# M709B.net
KiCad netlist of a schematic drawn in EAGLE
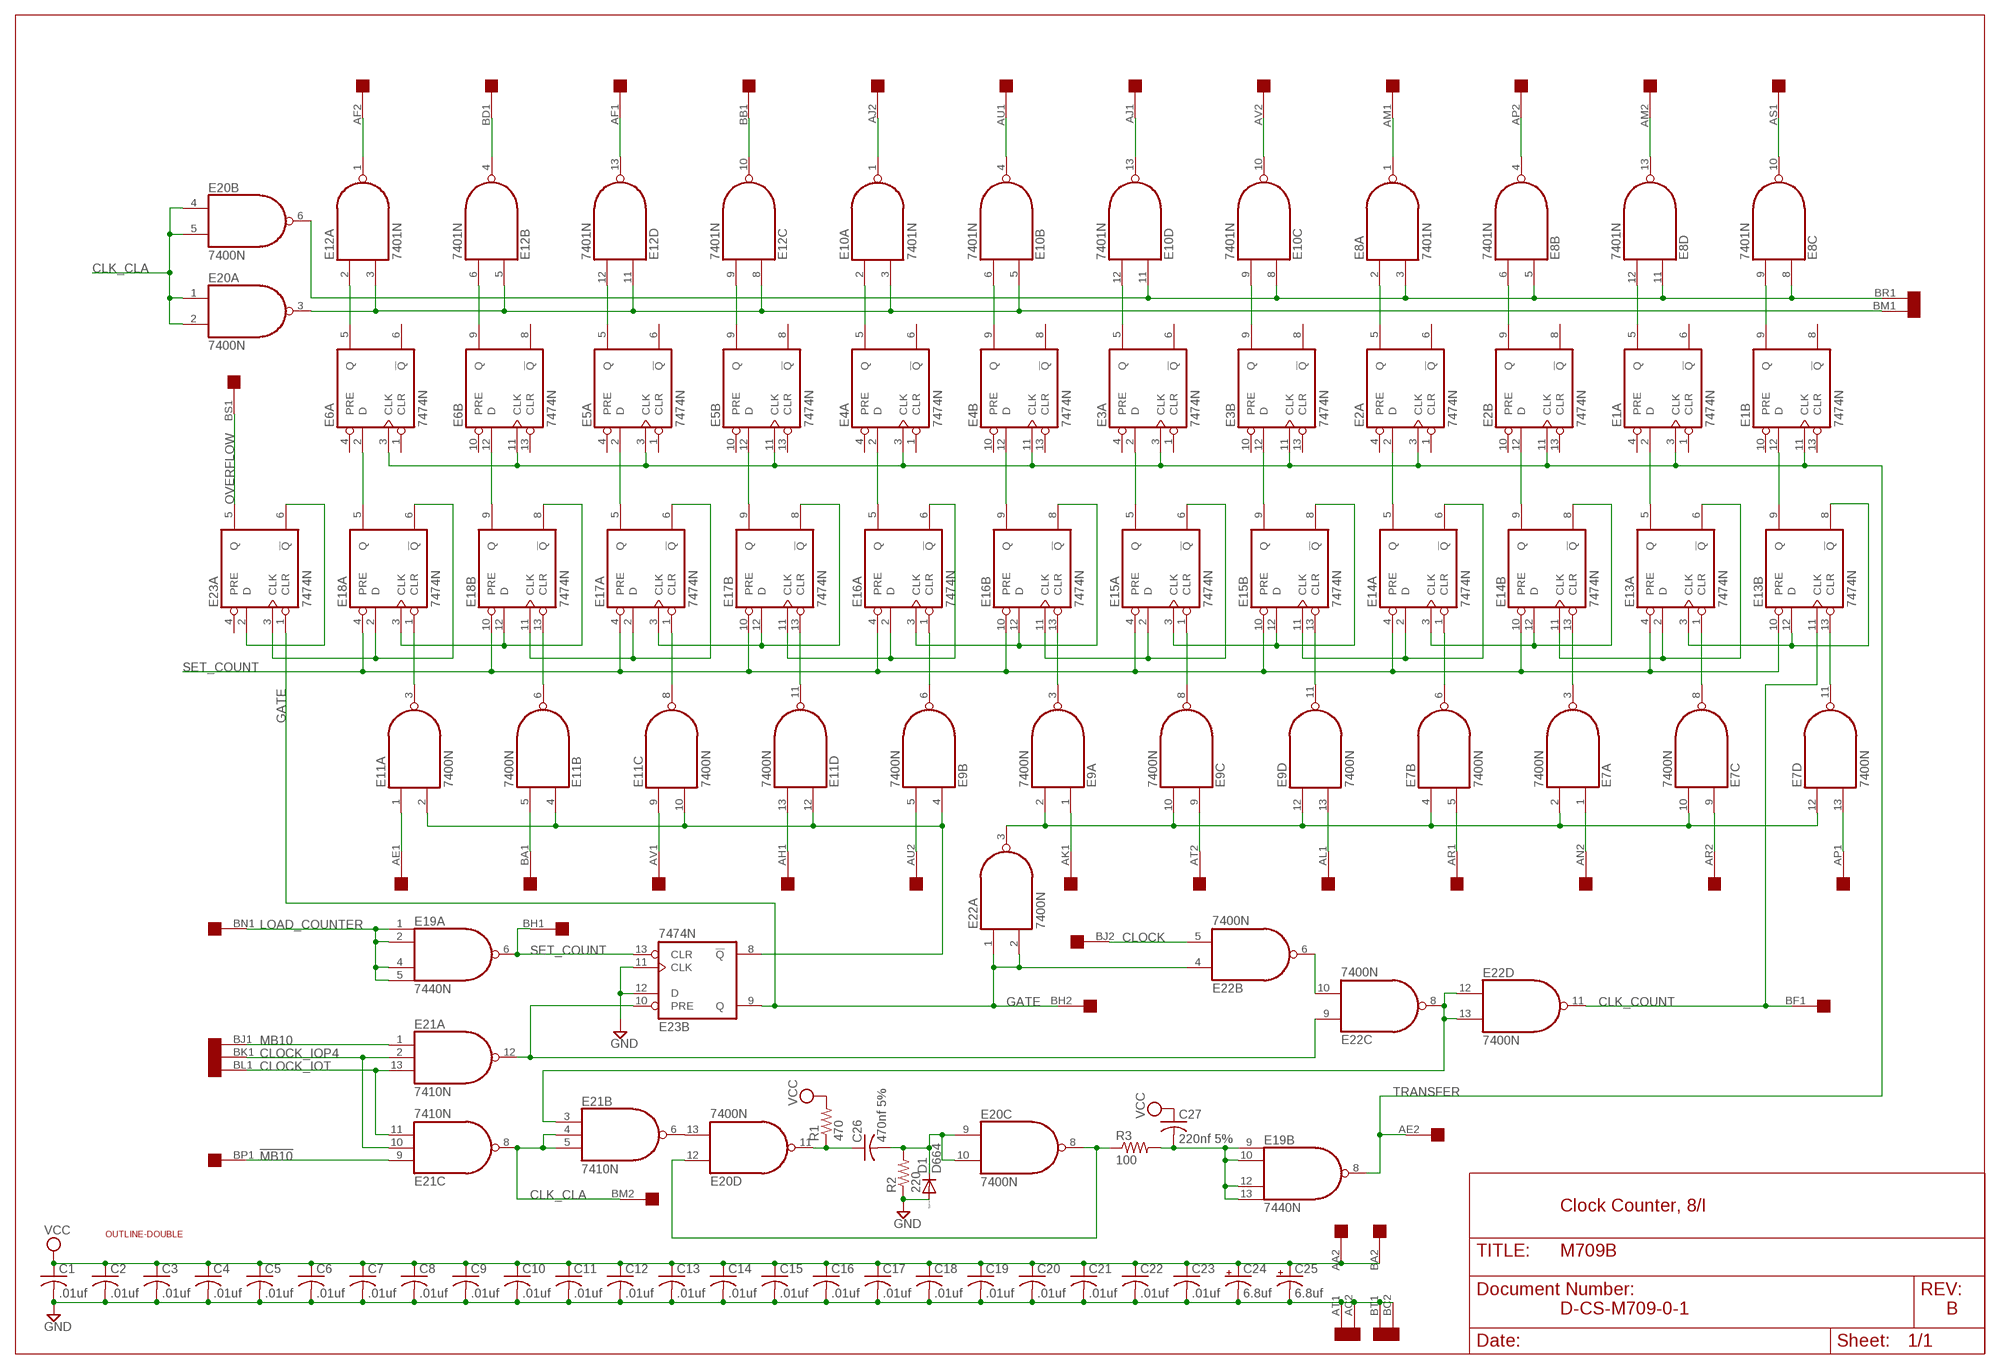
[diagram p0: schematic, sheet 1]

(export (version "E")
  (design (tool "Eeschema 10.0.6"))
  (components
    (comp (ref "C1")
      (value ".01uf")
      (footprint "eagle-import:C050-025X075")
      (libsource (lib "eagle-import") (part "C-US050-025X075"))
    )
    (comp (ref "C2")
      (value ".01uf")
      (footprint "eagle-import:C050-025X075")
      (libsource (lib "eagle-import") (part "C-US050-025X075"))
    )
    (comp (ref "C3")
      (value ".01uf")
      (footprint "eagle-import:C050-025X075")
      (libsource (lib "eagle-import") (part "C-US050-025X075"))
    )
    (comp (ref "C4")
      (value ".01uf")
      (footprint "eagle-import:C050-025X075")
      (libsource (lib "eagle-import") (part "C-US050-025X075"))
    )
    (comp (ref "C5")
      (value ".01uf")
      (footprint "eagle-import:C050-025X075")
      (libsource (lib "eagle-import") (part "C-US050-025X075"))
    )
    (comp (ref "C6")
      (value ".01uf")
      (footprint "eagle-import:C050-025X075")
      (libsource (lib "eagle-import") (part "C-US050-025X075"))
    )
    (comp (ref "C7")
      (value ".01uf")
      (footprint "eagle-import:C050-025X075")
      (libsource (lib "eagle-import") (part "C-US050-025X075"))
    )
    (comp (ref "C8")
      (value ".01uf")
      (footprint "eagle-import:C050-025X075")
      (libsource (lib "eagle-import") (part "C-US050-025X075"))
    )
    (comp (ref "C9")
      (value ".01uf")
      (footprint "eagle-import:C050-025X075")
      (libsource (lib "eagle-import") (part "C-US050-025X075"))
    )
    (comp (ref "C10")
      (value ".01uf")
      (footprint "eagle-import:C050-025X075")
      (libsource (lib "eagle-import") (part "C-US050-025X075"))
    )
    (comp (ref "C11")
      (value ".01uf")
      (footprint "eagle-import:C050-025X075")
      (libsource (lib "eagle-import") (part "C-US050-025X075"))
    )
    (comp (ref "C12")
      (value ".01uf")
      (footprint "eagle-import:C050-025X075")
      (libsource (lib "eagle-import") (part "C-US050-025X075"))
    )
    (comp (ref "C13")
      (value ".01uf")
      (footprint "eagle-import:C050-025X075")
      (libsource (lib "eagle-import") (part "C-US050-025X075"))
    )
    (comp (ref "C14")
      (value ".01uf")
      (footprint "eagle-import:C050-025X075")
      (libsource (lib "eagle-import") (part "C-US050-025X075"))
    )
    (comp (ref "C15")
      (value ".01uf")
      (footprint "eagle-import:C050-025X075")
      (libsource (lib "eagle-import") (part "C-US050-025X075"))
    )
    (comp (ref "C16")
      (value ".01uf")
      (footprint "eagle-import:C050-025X075")
      (libsource (lib "eagle-import") (part "C-US050-025X075"))
    )
    (comp (ref "C17")
      (value ".01uf")
      (footprint "eagle-import:C050-025X075")
      (libsource (lib "eagle-import") (part "C-US050-025X075"))
    )
    (comp (ref "C18")
      (value ".01uf")
      (footprint "eagle-import:C050-025X075")
      (libsource (lib "eagle-import") (part "C-US050-025X075"))
    )
    (comp (ref "C19")
      (value ".01uf")
      (footprint "eagle-import:C050-025X075")
      (libsource (lib "eagle-import") (part "C-US050-025X075"))
    )
    (comp (ref "C20")
      (value ".01uf")
      (footprint "eagle-import:C050-025X075")
      (libsource (lib "eagle-import") (part "C-US050-025X075"))
    )
    (comp (ref "C21")
      (value ".01uf")
      (footprint "eagle-import:C050-025X075")
      (libsource (lib "eagle-import") (part "C-US050-025X075"))
    )
    (comp (ref "C22")
      (value ".01uf")
      (footprint "eagle-import:C050-025X075")
      (libsource (lib "eagle-import") (part "C-US050-025X075"))
    )
    (comp (ref "C23")
      (value ".01uf")
      (footprint "eagle-import:C050-025X075")
      (libsource (lib "eagle-import") (part "C-US050-025X075"))
    )
    (comp (ref "C24")
      (value "6.8uf")
      (footprint "eagle-import:E15-5")
      (libsource (lib "eagle-import") (part "CPOL-USE15-5AXIAL"))
    )
    (comp (ref "C25")
      (value "6.8uf")
      (footprint "eagle-import:E15-5")
      (libsource (lib "eagle-import") (part "CPOL-USE15-5AXIAL"))
    )
    (comp (ref "C26")
      (value "470nf 5%")
      (footprint "eagle-import:C050-025X075")
      (libsource (lib "eagle-import") (part "C-US050-025X075"))
    )
    (comp (ref "C27")
      (value "220nf 5%")
      (footprint "eagle-import:C050-025X075")
      (libsource (lib "eagle-import") (part "C-US050-025X075"))
    )
    (comp (ref "D1")
      (value "D664")
      (footprint "eagle-import:DO35-10")
      (libsource (lib "eagle-import") (part "1N4148DO35-10"))
    )
    (comp (ref "E1")
      (value "7474N")
      (footprint "eagle-import:DIL14")
      (libsource (lib "eagle-import") (part "7474NS"))
    )
    (comp (ref "E2")
      (value "7474N")
      (footprint "eagle-import:DIL14")
      (libsource (lib "eagle-import") (part "7474NS"))
    )
    (comp (ref "E3")
      (value "7474N")
      (footprint "eagle-import:DIL14")
      (libsource (lib "eagle-import") (part "7474NS"))
    )
    (comp (ref "E4")
      (value "7474N")
      (footprint "eagle-import:DIL14")
      (libsource (lib "eagle-import") (part "7474NS"))
    )
    (comp (ref "E5")
      (value "7474N")
      (footprint "eagle-import:DIL14")
      (libsource (lib "eagle-import") (part "7474NS"))
    )
    (comp (ref "E6")
      (value "7474N")
      (footprint "eagle-import:DIL14")
      (libsource (lib "eagle-import") (part "7474NS"))
    )
    (comp (ref "E7")
      (value "7400N")
      (footprint "eagle-import:DIL14")
      (libsource (lib "eagle-import") (part "7400N"))
    )
    (comp (ref "E8")
      (value "7401N")
      (footprint "eagle-import:DIL14")
      (libsource (lib "eagle-import") (part "7401NLS"))
    )
    (comp (ref "E9")
      (value "7400N")
      (footprint "eagle-import:DIL14")
      (libsource (lib "eagle-import") (part "7400N"))
    )
    (comp (ref "E10")
      (value "7401N")
      (footprint "eagle-import:DIL14")
      (libsource (lib "eagle-import") (part "7401NLS"))
    )
    (comp (ref "E11")
      (value "7400N")
      (footprint "eagle-import:DIL14")
      (libsource (lib "eagle-import") (part "7400N"))
    )
    (comp (ref "E12")
      (value "7401N")
      (footprint "eagle-import:DIL14")
      (libsource (lib "eagle-import") (part "7401NLS"))
    )
    (comp (ref "E13")
      (value "7474N")
      (footprint "eagle-import:DIL14")
      (libsource (lib "eagle-import") (part "7474NS"))
    )
    (comp (ref "E14")
      (value "7474N")
      (footprint "eagle-import:DIL14")
      (libsource (lib "eagle-import") (part "7474NS"))
    )
    (comp (ref "E15")
      (value "7474N")
      (footprint "eagle-import:DIL14")
      (libsource (lib "eagle-import") (part "7474NS"))
    )
    (comp (ref "E16")
      (value "7474N")
      (footprint "eagle-import:DIL14")
      (libsource (lib "eagle-import") (part "7474NS"))
    )
    (comp (ref "E17")
      (value "7474N")
      (footprint "eagle-import:DIL14")
      (libsource (lib "eagle-import") (part "7474NS"))
    )
    (comp (ref "E18")
      (value "7474N")
      (footprint "eagle-import:DIL14")
      (libsource (lib "eagle-import") (part "7474NS"))
    )
    (comp (ref "E19")
      (value "7440N")
      (footprint "eagle-import:DIL14")
      (libsource (lib "eagle-import") (part "7420NS"))
    )
    (comp (ref "E20")
      (value "7400N")
      (footprint "eagle-import:DIL14")
      (libsource (lib "eagle-import") (part "7400N"))
    )
    (comp (ref "E21")
      (value "7410N")
      (footprint "eagle-import:DIL14")
      (libsource (lib "eagle-import") (part "7410N"))
    )
    (comp (ref "E22")
      (value "7400N")
      (footprint "eagle-import:DIL14")
      (libsource (lib "eagle-import") (part "7400N"))
    )
    (comp (ref "E23")
      (value "7474N")
      (footprint "eagle-import:DIL14")
      (libsource (lib "eagle-import") (part "7474NS"))
    )
    (comp (ref "R1")
      (value "470")
      (footprint "eagle-import:0207_10")
      (libsource (lib "eagle-import") (part "R-US_0207/10"))
    )
    (comp (ref "R2")
      (value "220")
      (footprint "eagle-import:0207_10")
      (libsource (lib "eagle-import") (part "R-US_0207/10"))
    )
    (comp (ref "R3")
      (value "100")
      (footprint "eagle-import:0207_10")
      (libsource (lib "eagle-import") (part "R-US_0207/10"))
    )
    (comp (ref "U$1")
      (value "OUTLINE-DOUBLE")
      (footprint "eagle-import:DOUBLE")
      (libsource (lib "eagle-import") (part "OUTLINE-DOUBLE"))
    )
    (comp (ref "U$2")
      (value "DOUBLE")
      (footprint "eagle-import:EDGE-CON4")
      (libsource (lib "eagle-import") (part "DOUBLE"))
    )
  )
  (nets
    (net (code "1") (name "/CLK_CLA") (class "Default")
      (node (ref "E20") (pin "1") (pinfunction "I0_1") (pintype "input"))
      (node (ref "E20") (pin "2") (pinfunction "I1_2") (pintype "input"))
      (node (ref "E20") (pin "4") (pinfunction "I0_4") (pintype "input"))
      (node (ref "E20") (pin "5") (pinfunction "I1_5") (pintype "input"))
      (node (ref "E21") (pin "4") (pinfunction "I1_4") (pintype "input"))
      (node (ref "E21") (pin "5") (pinfunction "I2_5") (pintype "input"))
      (node (ref "E21") (pin "8") (pinfunction "O_8") (pintype "output"))
      (node (ref "U$2") (pin "BM2") (pinfunction "1_BM2") (pintype "bidirectional"))
    )
    (net (code "2") (name "/CLK_COUNT") (class "Default")
      (node (ref "E13") (pin "11") (pinfunction "CLK_11") (pintype "input"))
      (node (ref "E22") (pin "11") (pinfunction "O_11") (pintype "output"))
      (node (ref "U$2") (pin "BF1") (pinfunction "1_BF1") (pintype "bidirectional"))
    )
    (net (code "3") (name "/CLOCK") (class "Default")
      (node (ref "E22") (pin "5") (pinfunction "I1_5") (pintype "input"))
      (node (ref "U$2") (pin "BJ2") (pinfunction "1_BJ2") (pintype "bidirectional"))
    )
    (net (code "4") (name "/CLOCK_IOP4") (class "Default")
      (node (ref "E21") (pin "10") (pinfunction "I1_10") (pintype "input"))
      (node (ref "E21") (pin "2") (pinfunction "I1_2") (pintype "input"))
      (node (ref "U$2") (pin "BK1") (pinfunction "1_BK1") (pintype "bidirectional"))
    )
    (net (code "5") (name "/CLOCK_IOT") (class "Default")
      (node (ref "E21") (pin "11") (pinfunction "I2_11") (pintype "input"))
      (node (ref "E21") (pin "13") (pinfunction "I2_13") (pintype "input"))
      (node (ref "U$2") (pin "BL1") (pinfunction "1_BL1") (pintype "bidirectional"))
    )
    (net (code "6") (name "/GATE") (class "Default")
      (node (ref "E22") (pin "1") (pinfunction "I0_1") (pintype "input"))
      (node (ref "E22") (pin "2") (pinfunction "I1_2") (pintype "input"))
      (node (ref "E22") (pin "4") (pinfunction "I0_4") (pintype "input"))
      (node (ref "E23") (pin "1") (pinfunction "CLR_1") (pintype "input"))
      (node (ref "E23") (pin "9") (pinfunction "Q_9") (pintype "output"))
      (node (ref "U$2") (pin "BH2") (pinfunction "1_BH2") (pintype "bidirectional"))
    )
    (net (code "7") (name "/LOAD_COUNTER") (class "Default")
      (node (ref "E19") (pin "1") (pinfunction "I0_1") (pintype "input"))
      (node (ref "E19") (pin "2") (pinfunction "I1_2") (pintype "input"))
      (node (ref "E19") (pin "4") (pinfunction "I2_4") (pintype "input"))
      (node (ref "E19") (pin "5") (pinfunction "I3_5") (pintype "input"))
      (node (ref "U$2") (pin "BN1") (pinfunction "1_BN1") (pintype "bidirectional"))
    )
    (net (code "8") (name "/MB10") (class "Default")
      (node (ref "E21") (pin "1") (pinfunction "I0_1") (pintype "input"))
      (node (ref "U$2") (pin "BJ1") (pinfunction "1_BJ1") (pintype "bidirectional"))
    )
    (net (code "9") (name "/OVERFLOW") (class "Default")
      (node (ref "E23") (pin "5") (pinfunction "Q_5") (pintype "output"))
      (node (ref "U$2") (pin "BS1") (pinfunction "1_BS1") (pintype "bidirectional"))
    )
    (net (code "10") (name "/SET_COUNT") (class "Default")
      (node (ref "E13") (pin "10") (pinfunction "PRE_10") (pintype "input"))
      (node (ref "E13") (pin "4") (pinfunction "PRE_4") (pintype "input"))
      (node (ref "E14") (pin "10") (pinfunction "PRE_10") (pintype "input"))
      (node (ref "E14") (pin "4") (pinfunction "PRE_4") (pintype "input"))
      (node (ref "E15") (pin "10") (pinfunction "PRE_10") (pintype "input"))
      (node (ref "E15") (pin "4") (pinfunction "PRE_4") (pintype "input"))
      (node (ref "E16") (pin "10") (pinfunction "PRE_10") (pintype "input"))
      (node (ref "E16") (pin "4") (pinfunction "PRE_4") (pintype "input"))
      (node (ref "E17") (pin "10") (pinfunction "PRE_10") (pintype "input"))
      (node (ref "E17") (pin "4") (pinfunction "PRE_4") (pintype "input"))
      (node (ref "E18") (pin "10") (pinfunction "PRE_10") (pintype "input"))
      (node (ref "E18") (pin "4") (pinfunction "PRE_4") (pintype "input"))
      (node (ref "E19") (pin "6") (pinfunction "O_6") (pintype "output"))
      (node (ref "E23") (pin "13") (pinfunction "CLR_13") (pintype "input"))
      (node (ref "U$2") (pin "BH1") (pinfunction "1_BH1") (pintype "bidirectional"))
    )
    (net (code "11") (name "/TRANSFER") (class "Default")
      (node (ref "E1") (pin "11") (pinfunction "CLK_11") (pintype "input"))
      (node (ref "E1") (pin "3") (pinfunction "CLK_3") (pintype "input"))
      (node (ref "E19") (pin "8") (pinfunction "O_8") (pintype "output"))
      (node (ref "E2") (pin "11") (pinfunction "CLK_11") (pintype "input"))
      (node (ref "E2") (pin "3") (pinfunction "CLK_3") (pintype "input"))
      (node (ref "E3") (pin "11") (pinfunction "CLK_11") (pintype "input"))
      (node (ref "E3") (pin "3") (pinfunction "CLK_3") (pintype "input"))
      (node (ref "E4") (pin "11") (pinfunction "CLK_11") (pintype "input"))
      (node (ref "E4") (pin "3") (pinfunction "CLK_3") (pintype "input"))
      (node (ref "E5") (pin "11") (pinfunction "CLK_11") (pintype "input"))
      (node (ref "E5") (pin "3") (pinfunction "CLK_3") (pintype "input"))
      (node (ref "E6") (pin "11") (pinfunction "CLK_11") (pintype "input"))
      (node (ref "E6") (pin "3") (pinfunction "CLK_3") (pintype "input"))
      (node (ref "U$2") (pin "AE2") (pinfunction "1_AE2") (pintype "bidirectional"))
    )
    (net (code "12") (name "/~{MB10}") (class "Default")
      (node (ref "E21") (pin "9") (pinfunction "I0_9") (pintype "input"))
      (node (ref "U$2") (pin "BP1") (pinfunction "1_BP1") (pintype "bidirectional"))
    )
    (net (code "13") (name "GND") (class "Default")
      (node (ref "C1") (pin "2") (pinfunction "2_2") (pintype "passive"))
      (node (ref "C10") (pin "2") (pinfunction "2_2") (pintype "passive"))
      (node (ref "C11") (pin "2") (pinfunction "2_2") (pintype "passive"))
      (node (ref "C12") (pin "2") (pinfunction "2_2") (pintype "passive"))
      (node (ref "C13") (pin "2") (pinfunction "2_2") (pintype "passive"))
      (node (ref "C14") (pin "2") (pinfunction "2_2") (pintype "passive"))
      (node (ref "C15") (pin "2") (pinfunction "2_2") (pintype "passive"))
      (node (ref "C16") (pin "2") (pinfunction "2_2") (pintype "passive"))
      (node (ref "C17") (pin "2") (pinfunction "2_2") (pintype "passive"))
      (node (ref "C18") (pin "2") (pinfunction "2_2") (pintype "passive"))
      (node (ref "C19") (pin "2") (pinfunction "2_2") (pintype "passive"))
      (node (ref "C2") (pin "2") (pinfunction "2_2") (pintype "passive"))
      (node (ref "C20") (pin "2") (pinfunction "2_2") (pintype "passive"))
      (node (ref "C21") (pin "2") (pinfunction "2_2") (pintype "passive"))
      (node (ref "C22") (pin "2") (pinfunction "2_2") (pintype "passive"))
      (node (ref "C23") (pin "2") (pinfunction "2_2") (pintype "passive"))
      (node (ref "C24") (pin "-") (pinfunction "-_-") (pintype "passive"))
      (node (ref "C25") (pin "-") (pinfunction "-_-") (pintype "passive"))
      (node (ref "C3") (pin "2") (pinfunction "2_2") (pintype "passive"))
      (node (ref "C4") (pin "2") (pinfunction "2_2") (pintype "passive"))
      (node (ref "C5") (pin "2") (pinfunction "2_2") (pintype "passive"))
      (node (ref "C6") (pin "2") (pinfunction "2_2") (pintype "passive"))
      (node (ref "C7") (pin "2") (pinfunction "2_2") (pintype "passive"))
      (node (ref "C8") (pin "2") (pinfunction "2_2") (pintype "passive"))
      (node (ref "C9") (pin "2") (pinfunction "2_2") (pintype "passive"))
      (node (ref "D1") (pin "A") (pinfunction "A_A") (pintype "passive"))
      (node (ref "E23") (pin "11") (pinfunction "CLK_11") (pintype "input"))
      (node (ref "E23") (pin "12") (pinfunction "D_12") (pintype "input"))
      (node (ref "R2") (pin "1") (pinfunction "1_1") (pintype "passive"))
      (node (ref "U$2") (pin "AC2") (pinfunction "1_AC2") (pintype "bidirectional"))
      (node (ref "U$2") (pin "AT1") (pinfunction "1_AT1") (pintype "bidirectional"))
      (node (ref "U$2") (pin "BC2") (pinfunction "1_BC2") (pintype "bidirectional"))
      (node (ref "U$2") (pin "BT1") (pinfunction "1_BT1") (pintype "bidirectional"))
    )
    (net (code "14") (name "Net-(E1A-Q)") (class "Default")
      (node (ref "E1") (pin "5") (pinfunction "Q_5") (pintype "output"))
      (node (ref "E8") (pin "12") (pinfunction "I1_12") (pintype "input"))
    )
    (net (code "15") (name "Net-(E1B-Q)") (class "Default")
      (node (ref "E1") (pin "9") (pinfunction "Q_9") (pintype "output"))
      (node (ref "E8") (pin "9") (pinfunction "I1_9") (pintype "input"))
    )
    (net (code "16") (name "Net-(E2A-Q)") (class "Default")
      (node (ref "E2") (pin "5") (pinfunction "Q_5") (pintype "output"))
      (node (ref "E8") (pin "2") (pinfunction "I0_2") (pintype "input"))
    )
    (net (code "17") (name "Net-(E2B-Q)") (class "Default")
      (node (ref "E2") (pin "9") (pinfunction "Q_9") (pintype "output"))
      (node (ref "E8") (pin "6") (pinfunction "I1_6") (pintype "input"))
    )
    (net (code "18") (name "Net-(E7A-I0)") (class "Default")
      (node (ref "E7") (pin "1") (pinfunction "I0_1") (pintype "input"))
      (node (ref "U$2") (pin "AN2") (pinfunction "1_AN2") (pintype "bidirectional"))
    )
    (net (code "19") (name "Net-(E7B-I1)") (class "Default")
      (node (ref "E7") (pin "5") (pinfunction "I1_5") (pintype "input"))
      (node (ref "U$2") (pin "AR1") (pinfunction "1_AR1") (pintype "bidirectional"))
    )
    (net (code "20") (name "Net-(E7C-I0)") (class "Default")
      (node (ref "E7") (pin "9") (pinfunction "I0_9") (pintype "input"))
      (node (ref "U$2") (pin "AR2") (pinfunction "1_AR2") (pintype "bidirectional"))
    )
    (net (code "21") (name "Net-(E7D-I1)") (class "Default")
      (node (ref "E7") (pin "13") (pinfunction "I1_13") (pintype "input"))
      (node (ref "U$2") (pin "AP1") (pinfunction "1_AP1") (pintype "bidirectional"))
    )
    (net (code "22") (name "Net-(E8A-O)") (class "Default")
      (node (ref "E8") (pin "1") (pinfunction "O_1") (pintype "open_collector"))
      (node (ref "U$2") (pin "AM1") (pinfunction "1_AM1") (pintype "bidirectional"))
    )
    (net (code "23") (name "Net-(E8B-O)") (class "Default")
      (node (ref "E8") (pin "4") (pinfunction "O_4") (pintype "open_collector"))
      (node (ref "U$2") (pin "AP2") (pinfunction "1_AP2") (pintype "bidirectional"))
    )
    (net (code "24") (name "Net-(E8C-O)") (class "Default")
      (node (ref "E8") (pin "10") (pinfunction "O_10") (pintype "open_collector"))
      (node (ref "U$2") (pin "AS1") (pinfunction "1_AS1") (pintype "bidirectional"))
    )
    (net (code "25") (name "Net-(E8D-O)") (class "Default")
      (node (ref "E8") (pin "13") (pinfunction "O_13") (pintype "open_collector"))
      (node (ref "U$2") (pin "AM2") (pinfunction "1_AM2") (pintype "bidirectional"))
    )
    (net (code "26") (name "Net-(E9A-I0)") (class "Default")
      (node (ref "E9") (pin "1") (pinfunction "I0_1") (pintype "input"))
      (node (ref "U$2") (pin "AK1") (pinfunction "1_AK1") (pintype "bidirectional"))
    )
    (net (code "27") (name "Net-(E9B-I1)") (class "Default")
      (node (ref "E9") (pin "5") (pinfunction "I1_5") (pintype "input"))
      (node (ref "U$2") (pin "AU2") (pinfunction "1_AU2") (pintype "bidirectional"))
    )
    (net (code "28") (name "Net-(E9C-I0)") (class "Default")
      (node (ref "E9") (pin "9") (pinfunction "I0_9") (pintype "input"))
      (node (ref "U$2") (pin "AT2") (pinfunction "1_AT2") (pintype "bidirectional"))
    )
    (net (code "29") (name "Net-(E9D-I1)") (class "Default")
      (node (ref "E9") (pin "13") (pinfunction "I1_13") (pintype "input"))
      (node (ref "U$2") (pin "AL1") (pinfunction "1_AL1") (pintype "bidirectional"))
    )
    (net (code "30") (name "Net-(E10A-I0)") (class "Default")
      (node (ref "E10") (pin "2") (pinfunction "I0_2") (pintype "input"))
      (node (ref "E4") (pin "5") (pinfunction "Q_5") (pintype "output"))
    )
    (net (code "31") (name "Net-(E10A-I1)") (class "Default")
      (node (ref "E10") (pin "3") (pinfunction "I1_3") (pintype "input"))
      (node (ref "E10") (pin "5") (pinfunction "I0_5") (pintype "input"))
      (node (ref "E12") (pin "11") (pinfunction "I0_11") (pintype "input"))
      (node (ref "E12") (pin "3") (pinfunction "I1_3") (pintype "input"))
      (node (ref "E12") (pin "5") (pinfunction "I0_5") (pintype "input"))
      (node (ref "E12") (pin "8") (pinfunction "I0_8") (pintype "input"))
      (node (ref "E20") (pin "3") (pinfunction "O_3") (pintype "output"))
      (node (ref "U$2") (pin "BM1") (pinfunction "1_BM1") (pintype "bidirectional"))
    )
    (net (code "32") (name "Net-(E10A-O)") (class "Default")
      (node (ref "E10") (pin "1") (pinfunction "O_1") (pintype "open_collector"))
      (node (ref "U$2") (pin "AJ2") (pinfunction "1_AJ2") (pintype "bidirectional"))
    )
    (net (code "33") (name "Net-(E10B-I1)") (class "Default")
      (node (ref "E10") (pin "6") (pinfunction "I1_6") (pintype "input"))
      (node (ref "E4") (pin "9") (pinfunction "Q_9") (pintype "output"))
    )
    (net (code "34") (name "Net-(E10B-O)") (class "Default")
      (node (ref "E10") (pin "4") (pinfunction "O_4") (pintype "open_collector"))
      (node (ref "U$2") (pin "AU1") (pinfunction "1_AU1") (pintype "bidirectional"))
    )
    (net (code "35") (name "Net-(E10C-I0)") (class "Default")
      (node (ref "E10") (pin "11") (pinfunction "I0_11") (pintype "input"))
      (node (ref "E10") (pin "8") (pinfunction "I0_8") (pintype "input"))
      (node (ref "E20") (pin "6") (pinfunction "O_6") (pintype "output"))
      (node (ref "E8") (pin "11") (pinfunction "I0_11") (pintype "input"))
      (node (ref "E8") (pin "3") (pinfunction "I1_3") (pintype "input"))
      (node (ref "E8") (pin "5") (pinfunction "I0_5") (pintype "input"))
      (node (ref "E8") (pin "8") (pinfunction "I0_8") (pintype "input"))
      (node (ref "U$2") (pin "BR1") (pinfunction "1_BR1") (pintype "bidirectional"))
    )
    (net (code "36") (name "Net-(E10C-I1)") (class "Default")
      (node (ref "E10") (pin "9") (pinfunction "I1_9") (pintype "input"))
      (node (ref "E3") (pin "9") (pinfunction "Q_9") (pintype "output"))
    )
    (net (code "37") (name "Net-(E10C-O)") (class "Default")
      (node (ref "E10") (pin "10") (pinfunction "O_10") (pintype "open_collector"))
      (node (ref "U$2") (pin "AV2") (pinfunction "1_AV2") (pintype "bidirectional"))
    )
    (net (code "38") (name "Net-(E10D-I1)") (class "Default")
      (node (ref "E10") (pin "12") (pinfunction "I1_12") (pintype "input"))
      (node (ref "E3") (pin "5") (pinfunction "Q_5") (pintype "output"))
    )
    (net (code "39") (name "Net-(E10D-O)") (class "Default")
      (node (ref "E10") (pin "13") (pinfunction "O_13") (pintype "open_collector"))
      (node (ref "U$2") (pin "AJ1") (pinfunction "1_AJ1") (pintype "bidirectional"))
    )
    (net (code "40") (name "Net-(E11A-I0)") (class "Default")
      (node (ref "E11") (pin "1") (pinfunction "I0_1") (pintype "input"))
      (node (ref "U$2") (pin "AE1") (pinfunction "1_AE1") (pintype "bidirectional"))
    )
    (net (code "41") (name "Net-(E11A-I1)") (class "Default")
      (node (ref "E11") (pin "10") (pinfunction "I1_10") (pintype "input"))
      (node (ref "E11") (pin "12") (pinfunction "I0_12") (pintype "input"))
      (node (ref "E11") (pin "2") (pinfunction "I1_2") (pintype "input"))
      (node (ref "E11") (pin "4") (pinfunction "I0_4") (pintype "input"))
      (node (ref "E23") (pin "8") (pinfunction "~{Q}_8") (pintype "output"))
      (node (ref "E9") (pin "4") (pinfunction "I0_4") (pintype "input"))
    )
    (net (code "42") (name "Net-(E11A-O)") (class "Default")
      (node (ref "E11") (pin "3") (pinfunction "O_3") (pintype "output"))
      (node (ref "E18") (pin "1") (pinfunction "CLR_1") (pintype "input"))
    )
    (net (code "43") (name "Net-(E11B-I1)") (class "Default")
      (node (ref "E11") (pin "5") (pinfunction "I1_5") (pintype "input"))
      (node (ref "U$2") (pin "BA1") (pinfunction "1_BA1") (pintype "bidirectional"))
    )
    (net (code "44") (name "Net-(E11B-O)") (class "Default")
      (node (ref "E11") (pin "6") (pinfunction "O_6") (pintype "output"))
      (node (ref "E18") (pin "13") (pinfunction "CLR_13") (pintype "input"))
    )
    (net (code "45") (name "Net-(E11C-I0)") (class "Default")
      (node (ref "E11") (pin "9") (pinfunction "I0_9") (pintype "input"))
      (node (ref "U$2") (pin "AV1") (pinfunction "1_AV1") (pintype "bidirectional"))
    )
    (net (code "46") (name "Net-(E11C-O)") (class "Default")
      (node (ref "E11") (pin "8") (pinfunction "O_8") (pintype "output"))
      (node (ref "E17") (pin "1") (pinfunction "CLR_1") (pintype "input"))
    )
    (net (code "47") (name "Net-(E11D-I1)") (class "Default")
      (node (ref "E11") (pin "13") (pinfunction "I1_13") (pintype "input"))
      (node (ref "U$2") (pin "AH1") (pinfunction "1_AH1") (pintype "bidirectional"))
    )
    (net (code "48") (name "Net-(E11D-O)") (class "Default")
      (node (ref "E11") (pin "11") (pinfunction "O_11") (pintype "output"))
      (node (ref "E17") (pin "13") (pinfunction "CLR_13") (pintype "input"))
    )
    (net (code "49") (name "Net-(E12A-I0)") (class "Default")
      (node (ref "E12") (pin "2") (pinfunction "I0_2") (pintype "input"))
      (node (ref "E6") (pin "5") (pinfunction "Q_5") (pintype "output"))
    )
    (net (code "50") (name "Net-(E12A-O)") (class "Default")
      (node (ref "E12") (pin "1") (pinfunction "O_1") (pintype "open_collector"))
      (node (ref "U$2") (pin "AF2") (pinfunction "1_AF2") (pintype "bidirectional"))
    )
    (net (code "51") (name "Net-(E12B-I1)") (class "Default")
      (node (ref "E12") (pin "6") (pinfunction "I1_6") (pintype "input"))
      (node (ref "E6") (pin "9") (pinfunction "Q_9") (pintype "output"))
    )
    (net (code "52") (name "Net-(E12B-O)") (class "Default")
      (node (ref "E12") (pin "4") (pinfunction "O_4") (pintype "open_collector"))
      (node (ref "U$2") (pin "BD1") (pinfunction "1_BD1") (pintype "bidirectional"))
    )
    (net (code "53") (name "Net-(E12C-I1)") (class "Default")
      (node (ref "E12") (pin "9") (pinfunction "I1_9") (pintype "input"))
      (node (ref "E5") (pin "9") (pinfunction "Q_9") (pintype "output"))
    )
    (net (code "54") (name "Net-(E12C-O)") (class "Default")
      (node (ref "E12") (pin "10") (pinfunction "O_10") (pintype "open_collector"))
      (node (ref "U$2") (pin "BB1") (pinfunction "1_BB1") (pintype "bidirectional"))
    )
    (net (code "55") (name "Net-(E12D-I1)") (class "Default")
      (node (ref "E12") (pin "12") (pinfunction "I1_12") (pintype "input"))
      (node (ref "E5") (pin "5") (pinfunction "Q_5") (pintype "output"))
    )
    (net (code "56") (name "Net-(E12D-O)") (class "Default")
      (node (ref "E12") (pin "13") (pinfunction "O_13") (pintype "open_collector"))
      (node (ref "U$2") (pin "AF1") (pinfunction "1_AF1") (pintype "bidirectional"))
    )
    (net (code "57") (name "Net-(E13A-CLK)") (class "Default")
      (node (ref "E13") (pin "12") (pinfunction "D_12") (pintype "input"))
      (node (ref "E13") (pin "3") (pinfunction "CLK_3") (pintype "input"))
      (node (ref "E13") (pin "8") (pinfunction "~{Q}_8") (pintype "output"))
    )
    (net (code "58") (name "Net-(E13A-CLR)") (class "Default")
      (node (ref "E13") (pin "1") (pinfunction "CLR_1") (pintype "input"))
      (node (ref "E7") (pin "8") (pinfunction "O_8") (pintype "output"))
    )
    (net (code "59") (name "Net-(E13A-D)") (class "Default")
      (node (ref "E13") (pin "2") (pinfunction "D_2") (pintype "input"))
      (node (ref "E13") (pin "6") (pinfunction "~{Q}_6") (pintype "output"))
      (node (ref "E14") (pin "11") (pinfunction "CLK_11") (pintype "input"))
    )
    (net (code "60") (name "Net-(E13A-Q)") (class "Default")
      (node (ref "E1") (pin "2") (pinfunction "D_2") (pintype "input"))
      (node (ref "E13") (pin "5") (pinfunction "Q_5") (pintype "output"))
    )
    (net (code "61") (name "Net-(E13B-CLR)") (class "Default")
      (node (ref "E13") (pin "13") (pinfunction "CLR_13") (pintype "input"))
      (node (ref "E7") (pin "11") (pinfunction "O_11") (pintype "output"))
    )
    (net (code "62") (name "Net-(E13B-Q)") (class "Default")
      (node (ref "E1") (pin "12") (pinfunction "D_12") (pintype "input"))
      (node (ref "E13") (pin "9") (pinfunction "Q_9") (pintype "output"))
    )
    (net (code "63") (name "Net-(E14A-CLK)") (class "Default")
      (node (ref "E14") (pin "12") (pinfunction "D_12") (pintype "input"))
      (node (ref "E14") (pin "3") (pinfunction "CLK_3") (pintype "input"))
      (node (ref "E14") (pin "8") (pinfunction "~{Q}_8") (pintype "output"))
    )
    (net (code "64") (name "Net-(E14A-CLR)") (class "Default")
      (node (ref "E14") (pin "1") (pinfunction "CLR_1") (pintype "input"))
      (node (ref "E7") (pin "6") (pinfunction "O_6") (pintype "output"))
    )
    (net (code "65") (name "Net-(E14A-D)") (class "Default")
      (node (ref "E14") (pin "2") (pinfunction "D_2") (pintype "input"))
      (node (ref "E14") (pin "6") (pinfunction "~{Q}_6") (pintype "output"))
      (node (ref "E15") (pin "11") (pinfunction "CLK_11") (pintype "input"))
    )
    (net (code "66") (name "Net-(E14A-Q)") (class "Default")
      (node (ref "E14") (pin "5") (pinfunction "Q_5") (pintype "output"))
      (node (ref "E2") (pin "2") (pinfunction "D_2") (pintype "input"))
    )
    (net (code "67") (name "Net-(E14B-CLR)") (class "Default")
      (node (ref "E14") (pin "13") (pinfunction "CLR_13") (pintype "input"))
      (node (ref "E7") (pin "3") (pinfunction "O_3") (pintype "output"))
    )
    (net (code "68") (name "Net-(E14B-Q)") (class "Default")
      (node (ref "E14") (pin "9") (pinfunction "Q_9") (pintype "output"))
      (node (ref "E2") (pin "12") (pinfunction "D_12") (pintype "input"))
    )
    (net (code "69") (name "Net-(E15A-CLK)") (class "Default")
      (node (ref "E15") (pin "12") (pinfunction "D_12") (pintype "input"))
      (node (ref "E15") (pin "3") (pinfunction "CLK_3") (pintype "input"))
      (node (ref "E15") (pin "8") (pinfunction "~{Q}_8") (pintype "output"))
    )
    (net (code "70") (name "Net-(E15A-CLR)") (class "Default")
      (node (ref "E15") (pin "1") (pinfunction "CLR_1") (pintype "input"))
      (node (ref "E9") (pin "8") (pinfunction "O_8") (pintype "output"))
    )
    (net (code "71") (name "Net-(E15A-D)") (class "Default")
      (node (ref "E15") (pin "2") (pinfunction "D_2") (pintype "input"))
      (node (ref "E15") (pin "6") (pinfunction "~{Q}_6") (pintype "output"))
      (node (ref "E16") (pin "11") (pinfunction "CLK_11") (pintype "input"))
    )
    (net (code "72") (name "Net-(E15A-Q)") (class "Default")
      (node (ref "E15") (pin "5") (pinfunction "Q_5") (pintype "output"))
      (node (ref "E3") (pin "2") (pinfunction "D_2") (pintype "input"))
    )
    (net (code "73") (name "Net-(E15B-CLR)") (class "Default")
      (node (ref "E15") (pin "13") (pinfunction "CLR_13") (pintype "input"))
      (node (ref "E9") (pin "11") (pinfunction "O_11") (pintype "output"))
    )
    (net (code "74") (name "Net-(E15B-Q)") (class "Default")
      (node (ref "E15") (pin "9") (pinfunction "Q_9") (pintype "output"))
      (node (ref "E3") (pin "12") (pinfunction "D_12") (pintype "input"))
    )
    (net (code "75") (name "Net-(E16A-CLK)") (class "Default")
      (node (ref "E16") (pin "12") (pinfunction "D_12") (pintype "input"))
      (node (ref "E16") (pin "3") (pinfunction "CLK_3") (pintype "input"))
      (node (ref "E16") (pin "8") (pinfunction "~{Q}_8") (pintype "output"))
    )
    (net (code "76") (name "Net-(E16A-CLR)") (class "Default")
      (node (ref "E16") (pin "1") (pinfunction "CLR_1") (pintype "input"))
      (node (ref "E9") (pin "6") (pinfunction "O_6") (pintype "output"))
    )
    (net (code "77") (name "Net-(E16A-D)") (class "Default")
      (node (ref "E16") (pin "2") (pinfunction "D_2") (pintype "input"))
      (node (ref "E16") (pin "6") (pinfunction "~{Q}_6") (pintype "output"))
      (node (ref "E17") (pin "11") (pinfunction "CLK_11") (pintype "input"))
    )
    (net (code "78") (name "Net-(E16A-Q)") (class "Default")
      (node (ref "E16") (pin "5") (pinfunction "Q_5") (pintype "output"))
      (node (ref "E4") (pin "2") (pinfunction "D_2") (pintype "input"))
    )
    (net (code "79") (name "Net-(E16B-CLR)") (class "Default")
      (node (ref "E16") (pin "13") (pinfunction "CLR_13") (pintype "input"))
      (node (ref "E9") (pin "3") (pinfunction "O_3") (pintype "output"))
    )
    (net (code "80") (name "Net-(E16B-Q)") (class "Default")
      (node (ref "E16") (pin "9") (pinfunction "Q_9") (pintype "output"))
      (node (ref "E4") (pin "12") (pinfunction "D_12") (pintype "input"))
    )
    (net (code "81") (name "Net-(E17A-CLK)") (class "Default")
      (node (ref "E17") (pin "12") (pinfunction "D_12") (pintype "input"))
      (node (ref "E17") (pin "3") (pinfunction "CLK_3") (pintype "input"))
      (node (ref "E17") (pin "8") (pinfunction "~{Q}_8") (pintype "output"))
    )
    (net (code "82") (name "Net-(E17A-D)") (class "Default")
      (node (ref "E17") (pin "2") (pinfunction "D_2") (pintype "input"))
      (node (ref "E17") (pin "6") (pinfunction "~{Q}_6") (pintype "output"))
      (node (ref "E18") (pin "11") (pinfunction "CLK_11") (pintype "input"))
    )
    (net (code "83") (name "Net-(E17A-Q)") (class "Default")
      (node (ref "E17") (pin "5") (pinfunction "Q_5") (pintype "output"))
      (node (ref "E5") (pin "2") (pinfunction "D_2") (pintype "input"))
    )
    (net (code "84") (name "Net-(E17B-Q)") (class "Default")
      (node (ref "E17") (pin "9") (pinfunction "Q_9") (pintype "output"))
      (node (ref "E5") (pin "12") (pinfunction "D_12") (pintype "input"))
    )
    (net (code "85") (name "Net-(E18A-CLK)") (class "Default")
      (node (ref "E18") (pin "12") (pinfunction "D_12") (pintype "input"))
      (node (ref "E18") (pin "3") (pinfunction "CLK_3") (pintype "input"))
      (node (ref "E18") (pin "8") (pinfunction "~{Q}_8") (pintype "output"))
    )
    (net (code "86") (name "Net-(E18A-D)") (class "Default")
      (node (ref "E18") (pin "2") (pinfunction "D_2") (pintype "input"))
      (node (ref "E18") (pin "6") (pinfunction "~{Q}_6") (pintype "output"))
      (node (ref "E23") (pin "3") (pinfunction "CLK_3") (pintype "input"))
    )
    (net (code "87") (name "Net-(E18A-Q)") (class "Default")
      (node (ref "E18") (pin "5") (pinfunction "Q_5") (pintype "output"))
      (node (ref "E6") (pin "2") (pinfunction "D_2") (pintype "input"))
    )
    (net (code "88") (name "Net-(E18B-Q)") (class "Default")
      (node (ref "E18") (pin "9") (pinfunction "Q_9") (pintype "output"))
      (node (ref "E6") (pin "12") (pinfunction "D_12") (pintype "input"))
    )
    (net (code "89") (name "Net-(E19B-I0)") (class "Default")
      (node (ref "C27") (pin "2") (pinfunction "2_2") (pintype "passive"))
      (node (ref "E19") (pin "10") (pinfunction "I1_10") (pintype "input"))
      (node (ref "E19") (pin "12") (pinfunction "I2_12") (pintype "input"))
      (node (ref "E19") (pin "13") (pinfunction "I3_13") (pintype "input"))
      (node (ref "E19") (pin "9") (pinfunction "I0_9") (pintype "input"))
      (node (ref "R3") (pin "2") (pinfunction "2_2") (pintype "passive"))
    )
    (net (code "90") (name "Net-(E20C-I0)") (class "Default")
      (node (ref "C26") (pin "2") (pinfunction "2_2") (pintype "passive"))
      (node (ref "D1") (pin "C") (pinfunction "C_C") (pintype "passive"))
      (node (ref "E20") (pin "10") (pinfunction "I1_10") (pintype "input"))
      (node (ref "E20") (pin "9") (pinfunction "I0_9") (pintype "input"))
      (node (ref "R2") (pin "2") (pinfunction "2_2") (pintype "passive"))
    )
    (net (code "91") (name "Net-(E20C-O)") (class "Default")
      (node (ref "E20") (pin "12") (pinfunction "I0_12") (pintype "input"))
      (node (ref "E20") (pin "8") (pinfunction "O_8") (pintype "output"))
      (node (ref "R3") (pin "1") (pinfunction "1_1") (pintype "passive"))
    )
    (net (code "92") (name "Net-(E20D-I1)") (class "Default")
      (node (ref "E20") (pin "13") (pinfunction "I1_13") (pintype "input"))
      (node (ref "E21") (pin "6") (pinfunction "O_6") (pintype "output"))
    )
    (net (code "93") (name "Net-(E20D-O)") (class "Default")
      (node (ref "C26") (pin "1") (pinfunction "1_1") (pintype "passive"))
      (node (ref "E20") (pin "11") (pinfunction "O_11") (pintype "output"))
      (node (ref "R1") (pin "1") (pinfunction "1_1") (pintype "passive"))
    )
    (net (code "94") (name "Net-(E21A-O)") (class "Default")
      (node (ref "E21") (pin "12") (pinfunction "O_12") (pintype "output"))
      (node (ref "E22") (pin "9") (pinfunction "I0_9") (pintype "input"))
      (node (ref "E23") (pin "10") (pinfunction "PRE_10") (pintype "input"))
    )
    (net (code "95") (name "Net-(E21B-I0)") (class "Default")
      (node (ref "E21") (pin "3") (pinfunction "I0_3") (pintype "input"))
      (node (ref "E22") (pin "12") (pinfunction "I0_12") (pintype "input"))
      (node (ref "E22") (pin "13") (pinfunction "I1_13") (pintype "input"))
      (node (ref "E22") (pin "8") (pinfunction "O_8") (pintype "output"))
    )
    (net (code "96") (name "Net-(E22A-O)") (class "Default")
      (node (ref "E22") (pin "3") (pinfunction "O_3") (pintype "output"))
      (node (ref "E7") (pin "10") (pinfunction "I1_10") (pintype "input"))
      (node (ref "E7") (pin "12") (pinfunction "I0_12") (pintype "input"))
      (node (ref "E7") (pin "2") (pinfunction "I1_2") (pintype "input"))
      (node (ref "E7") (pin "4") (pinfunction "I0_4") (pintype "input"))
      (node (ref "E9") (pin "10") (pinfunction "I1_10") (pintype "input"))
      (node (ref "E9") (pin "12") (pinfunction "I0_12") (pintype "input"))
      (node (ref "E9") (pin "2") (pinfunction "I1_2") (pintype "input"))
    )
    (net (code "97") (name "Net-(E22B-O)") (class "Default")
      (node (ref "E22") (pin "10") (pinfunction "I1_10") (pintype "input"))
      (node (ref "E22") (pin "6") (pinfunction "O_6") (pintype "output"))
    )
    (net (code "98") (name "Net-(E23A-D)") (class "Default")
      (node (ref "E23") (pin "2") (pinfunction "D_2") (pintype "input"))
      (node (ref "E23") (pin "6") (pinfunction "~{Q}_6") (pintype "output"))
    )
    (net (code "99") (name "VCC") (class "Default")
      (node (ref "C1") (pin "1") (pinfunction "1_1") (pintype "passive"))
      (node (ref "C10") (pin "1") (pinfunction "1_1") (pintype "passive"))
      (node (ref "C11") (pin "1") (pinfunction "1_1") (pintype "passive"))
      (node (ref "C12") (pin "1") (pinfunction "1_1") (pintype "passive"))
      (node (ref "C13") (pin "1") (pinfunction "1_1") (pintype "passive"))
      (node (ref "C14") (pin "1") (pinfunction "1_1") (pintype "passive"))
      (node (ref "C15") (pin "1") (pinfunction "1_1") (pintype "passive"))
      (node (ref "C16") (pin "1") (pinfunction "1_1") (pintype "passive"))
      (node (ref "C17") (pin "1") (pinfunction "1_1") (pintype "passive"))
      (node (ref "C18") (pin "1") (pinfunction "1_1") (pintype "passive"))
      (node (ref "C19") (pin "1") (pinfunction "1_1") (pintype "passive"))
      (node (ref "C2") (pin "1") (pinfunction "1_1") (pintype "passive"))
      (node (ref "C20") (pin "1") (pinfunction "1_1") (pintype "passive"))
      (node (ref "C21") (pin "1") (pinfunction "1_1") (pintype "passive"))
      (node (ref "C22") (pin "1") (pinfunction "1_1") (pintype "passive"))
      (node (ref "C23") (pin "1") (pinfunction "1_1") (pintype "passive"))
      (node (ref "C24") (pin "+") (pinfunction "+_+") (pintype "passive"))
      (node (ref "C25") (pin "+") (pinfunction "+_+") (pintype "passive"))
      (node (ref "C27") (pin "1") (pinfunction "1_1") (pintype "passive"))
      (node (ref "C3") (pin "1") (pinfunction "1_1") (pintype "passive"))
      (node (ref "C4") (pin "1") (pinfunction "1_1") (pintype "passive"))
      (node (ref "C5") (pin "1") (pinfunction "1_1") (pintype "passive"))
      (node (ref "C6") (pin "1") (pinfunction "1_1") (pintype "passive"))
      (node (ref "C7") (pin "1") (pinfunction "1_1") (pintype "passive"))
      (node (ref "C8") (pin "1") (pinfunction "1_1") (pintype "passive"))
      (node (ref "C9") (pin "1") (pinfunction "1_1") (pintype "passive"))
      (node (ref "R1") (pin "2") (pinfunction "2_2") (pintype "passive"))
      (node (ref "U$2") (pin "AA2") (pinfunction "1_AA2") (pintype "bidirectional"))
      (node (ref "U$2") (pin "BA2") (pinfunction "1_BA2") (pintype "bidirectional"))
    )
    (net (code "100") (name "unconnected-(E1A-CLR-Pad1)") (class "Default")
      (node (ref "E1") (pin "1") (pinfunction "CLR_1") (pintype "input"))
    )
    (net (code "101") (name "unconnected-(E1A-PRE-Pad4)") (class "Default")
      (node (ref "E1") (pin "4") (pinfunction "PRE_4") (pintype "input"))
    )
    (net (code "102") (name "unconnected-(E1A-~{Q}-Pad6)") (class "Default")
      (node (ref "E1") (pin "6") (pinfunction "~{Q}_6") (pintype "output"))
    )
    (net (code "103") (name "unconnected-(E1B-CLR-Pad13)") (class "Default")
      (node (ref "E1") (pin "13") (pinfunction "CLR_13") (pintype "input"))
    )
    (net (code "104") (name "unconnected-(E1B-PRE-Pad10)") (class "Default")
      (node (ref "E1") (pin "10") (pinfunction "PRE_10") (pintype "input"))
    )
    (net (code "105") (name "unconnected-(E1B-~{Q}-Pad8)") (class "Default")
      (node (ref "E1") (pin "8") (pinfunction "~{Q}_8") (pintype "output"))
    )
    (net (code "106") (name "unconnected-(E2A-CLR-Pad1)") (class "Default")
      (node (ref "E2") (pin "1") (pinfunction "CLR_1") (pintype "input"))
    )
    (net (code "107") (name "unconnected-(E2A-PRE-Pad4)") (class "Default")
      (node (ref "E2") (pin "4") (pinfunction "PRE_4") (pintype "input"))
    )
    (net (code "108") (name "unconnected-(E2A-~{Q}-Pad6)") (class "Default")
      (node (ref "E2") (pin "6") (pinfunction "~{Q}_6") (pintype "output"))
    )
    (net (code "109") (name "unconnected-(E2B-CLR-Pad13)") (class "Default")
      (node (ref "E2") (pin "13") (pinfunction "CLR_13") (pintype "input"))
    )
    (net (code "110") (name "unconnected-(E2B-PRE-Pad10)") (class "Default")
      (node (ref "E2") (pin "10") (pinfunction "PRE_10") (pintype "input"))
    )
    (net (code "111") (name "unconnected-(E2B-~{Q}-Pad8)") (class "Default")
      (node (ref "E2") (pin "8") (pinfunction "~{Q}_8") (pintype "output"))
    )
    (net (code "112") (name "unconnected-(E3A-CLR-Pad1)") (class "Default")
      (node (ref "E3") (pin "1") (pinfunction "CLR_1") (pintype "input"))
    )
    (net (code "113") (name "unconnected-(E3A-PRE-Pad4)") (class "Default")
      (node (ref "E3") (pin "4") (pinfunction "PRE_4") (pintype "input"))
    )
    (net (code "114") (name "unconnected-(E3A-~{Q}-Pad6)") (class "Default")
      (node (ref "E3") (pin "6") (pinfunction "~{Q}_6") (pintype "output"))
    )
    (net (code "115") (name "unconnected-(E3B-CLR-Pad13)") (class "Default")
      (node (ref "E3") (pin "13") (pinfunction "CLR_13") (pintype "input"))
    )
    (net (code "116") (name "unconnected-(E3B-PRE-Pad10)") (class "Default")
      (node (ref "E3") (pin "10") (pinfunction "PRE_10") (pintype "input"))
    )
    (net (code "117") (name "unconnected-(E3B-~{Q}-Pad8)") (class "Default")
      (node (ref "E3") (pin "8") (pinfunction "~{Q}_8") (pintype "output"))
    )
    (net (code "118") (name "unconnected-(E4A-CLR-Pad1)") (class "Default")
      (node (ref "E4") (pin "1") (pinfunction "CLR_1") (pintype "input"))
    )
    (net (code "119") (name "unconnected-(E4A-PRE-Pad4)") (class "Default")
      (node (ref "E4") (pin "4") (pinfunction "PRE_4") (pintype "input"))
    )
    (net (code "120") (name "unconnected-(E4A-~{Q}-Pad6)") (class "Default")
      (node (ref "E4") (pin "6") (pinfunction "~{Q}_6") (pintype "output"))
    )
    (net (code "121") (name "unconnected-(E4B-CLR-Pad13)") (class "Default")
      (node (ref "E4") (pin "13") (pinfunction "CLR_13") (pintype "input"))
    )
    (net (code "122") (name "unconnected-(E4B-PRE-Pad10)") (class "Default")
      (node (ref "E4") (pin "10") (pinfunction "PRE_10") (pintype "input"))
    )
    (net (code "123") (name "unconnected-(E4B-~{Q}-Pad8)") (class "Default")
      (node (ref "E4") (pin "8") (pinfunction "~{Q}_8") (pintype "output"))
    )
    (net (code "124") (name "unconnected-(E5A-CLR-Pad1)") (class "Default")
      (node (ref "E5") (pin "1") (pinfunction "CLR_1") (pintype "input"))
    )
    (net (code "125") (name "unconnected-(E5A-PRE-Pad4)") (class "Default")
      (node (ref "E5") (pin "4") (pinfunction "PRE_4") (pintype "input"))
    )
    (net (code "126") (name "unconnected-(E5A-~{Q}-Pad6)") (class "Default")
      (node (ref "E5") (pin "6") (pinfunction "~{Q}_6") (pintype "output"))
    )
    (net (code "127") (name "unconnected-(E5B-CLR-Pad13)") (class "Default")
      (node (ref "E5") (pin "13") (pinfunction "CLR_13") (pintype "input"))
    )
    (net (code "128") (name "unconnected-(E5B-PRE-Pad10)") (class "Default")
      (node (ref "E5") (pin "10") (pinfunction "PRE_10") (pintype "input"))
    )
    (net (code "129") (name "unconnected-(E5B-~{Q}-Pad8)") (class "Default")
      (node (ref "E5") (pin "8") (pinfunction "~{Q}_8") (pintype "output"))
    )
    (net (code "130") (name "unconnected-(E6A-CLR-Pad1)") (class "Default")
      (node (ref "E6") (pin "1") (pinfunction "CLR_1") (pintype "input"))
    )
    (net (code "131") (name "unconnected-(E6A-PRE-Pad4)") (class "Default")
      (node (ref "E6") (pin "4") (pinfunction "PRE_4") (pintype "input"))
    )
    (net (code "132") (name "unconnected-(E6A-~{Q}-Pad6)") (class "Default")
      (node (ref "E6") (pin "6") (pinfunction "~{Q}_6") (pintype "output"))
    )
    (net (code "133") (name "unconnected-(E6B-CLR-Pad13)") (class "Default")
      (node (ref "E6") (pin "13") (pinfunction "CLR_13") (pintype "input"))
    )
    (net (code "134") (name "unconnected-(E6B-PRE-Pad10)") (class "Default")
      (node (ref "E6") (pin "10") (pinfunction "PRE_10") (pintype "input"))
    )
    (net (code "135") (name "unconnected-(E6B-~{Q}-Pad8)") (class "Default")
      (node (ref "E6") (pin "8") (pinfunction "~{Q}_8") (pintype "output"))
    )
    (net (code "136") (name "unconnected-(E23A-PRE-Pad4)") (class "Default")
      (node (ref "E23") (pin "4") (pinfunction "PRE_4") (pintype "input"))
    )
  )
)
